# SD.net
KiCad netlist of a schematic drawn in Altium Designer
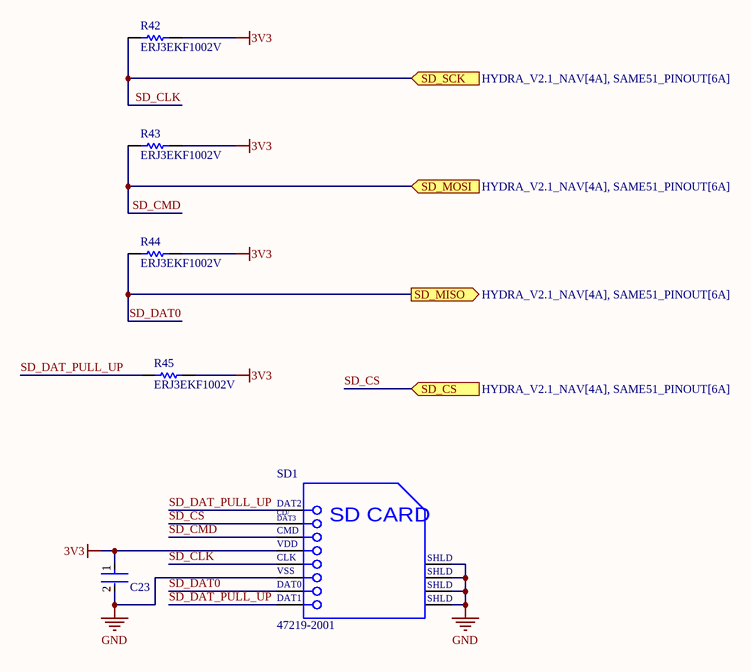
[diagram p0: SD.SchDoc]

(export (version "E")
  (design (tool "Eeschema 10.0.6"))
  (components
    (comp (ref "C23")
      (value "C0402C104K8PACTU")
      (footprint "FP-C0402-BB-MFG")
      (description "CAP CER 0.1UF 10V X5R 0402")
      (fields (field (name "MANUFACTURER") "Kemet") (field (name "TOLERANCE") "0.1"))
      (libsource (lib "Altium Content Vault") (part "b4654b650e69147ec39a6b967a45e02"))
    )
    (comp (ref "R42")
      (value "ERJ3EKF1002V")
      (footprint "RESC1609X55X30LL15T15")
      (description "Chip Resistor, 10 KOhm, +/- 1%, 0.1 W, -55 to 155 degC, 0603 (1608 Metric), RoHS, Tape and Reel")
      (fields (field (name "TOLERANCE") "1%") (field (name "MANUFACTURER") "Panasonic"))
      (libsource (lib "Altium Content Vault") (part "RES-2"))
    )
    (comp (ref "R43")
      (value "ERJ3EKF1002V")
      (footprint "RESC1609X55X30LL15T15")
      (description "Chip Resistor, 10 KOhm, +/- 1%, 0.1 W, -55 to 155 degC, 0603 (1608 Metric), RoHS, Tape and Reel")
      (fields (field (name "TOLERANCE") "1%") (field (name "MANUFACTURER") "Panasonic"))
      (libsource (lib "Altium Content Vault") (part "RES-2"))
    )
    (comp (ref "R44")
      (value "ERJ3EKF1002V")
      (footprint "RESC1609X55X30LL15T15")
      (description "Chip Resistor, 10 KOhm, +/- 1%, 0.1 W, -55 to 155 degC, 0603 (1608 Metric), RoHS, Tape and Reel")
      (fields (field (name "TOLERANCE") "1%") (field (name "MANUFACTURER") "Panasonic"))
      (libsource (lib "Altium Content Vault") (part "RES-2"))
    )
    (comp (ref "R45")
      (value "ERJ3EKF1002V")
      (footprint "RESC1609X55X30LL15T15")
      (description "Chip Resistor, 10 KOhm, +/- 1%, 0.1 W, -55 to 155 degC, 0603 (1608 Metric), RoHS, Tape and Reel")
      (fields (field (name "TOLERANCE") "1%") (field (name "MANUFACTURER") "Panasonic"))
      (libsource (lib "Altium Content Vault") (part "RES-2"))
    )
    (comp (ref "SD1")
      (value "47219-2001")
      (footprint "MOLX-47219-2001-8_V")
      (description "MicroSD Card Connector, Hinge Type, -40 to 85 degC, 8-Pin SMD, RoHS, Tape and Reel")
      (fields (field (name "MANUFACTURER") "Molex"))
      (libsource (lib "Altium Content Vault") (part "CN-SD-8-4S"))
    )
  )
  (nets
    (net (code "1") (name "/SD_CLK") (class "Default")
      (node (ref "R42") (pin "1") (pinfunction "1_1") (pintype "passive"))
      (node (ref "SD1") (pin "5") (pinfunction "CLK_5") (pintype "passive"))
    )
    (net (code "2") (name "/SD_CMD") (class "Default")
      (node (ref "R43") (pin "1") (pinfunction "1_1") (pintype "passive"))
      (node (ref "SD1") (pin "3") (pinfunction "CMD_3") (pintype "passive"))
    )
    (net (code "3") (name "/SD_CS") (class "Default")
      (node (ref "SD1") (pin "2") (pinfunction "CD/DAT3_2") (pintype "passive"))
    )
    (net (code "4") (name "/SD_DAT0") (class "Default")
      (node (ref "R44") (pin "1") (pinfunction "1_1") (pintype "passive"))
      (node (ref "SD1") (pin "7") (pinfunction "DAT0_7") (pintype "passive"))
    )
    (net (code "5") (name "/SD_DAT_PULL_UP") (class "Default")
      (node (ref "R45") (pin "1") (pinfunction "1_1") (pintype "passive"))
      (node (ref "SD1") (pin "1") (pinfunction "DAT2_1") (pintype "passive"))
      (node (ref "SD1") (pin "8") (pinfunction "DAT1_8") (pintype "passive"))
    )
    (net (code "6") (name "3V3") (class "Default")
      (node (ref "C23") (pin "1") (pinfunction "1_1") (pintype "passive"))
      (node (ref "R42") (pin "2") (pinfunction "2_2") (pintype "passive"))
      (node (ref "R43") (pin "2") (pinfunction "2_2") (pintype "passive"))
      (node (ref "R44") (pin "2") (pinfunction "2_2") (pintype "passive"))
      (node (ref "R45") (pin "2") (pinfunction "2_2") (pintype "passive"))
      (node (ref "SD1") (pin "4") (pinfunction "VDD_4") (pintype "passive"))
    )
    (net (code "7") (name "GND") (class "Default")
      (node (ref "C23") (pin "2") (pinfunction "2_2") (pintype "passive"))
      (node (ref "SD1") (pin "10") (pinfunction "SHLD_10") (pintype "passive"))
      (node (ref "SD1") (pin "11") (pinfunction "SHLD_11") (pintype "passive"))
      (node (ref "SD1") (pin "12") (pinfunction "SHLD_12") (pintype "passive"))
      (node (ref "SD1") (pin "6") (pinfunction "VSS_6") (pintype "passive"))
      (node (ref "SD1") (pin "9") (pinfunction "SHLD_9") (pintype "passive"))
    )
  )
)
